# Microcontroller.net
KiCad netlist of a schematic drawn in Altium Designer
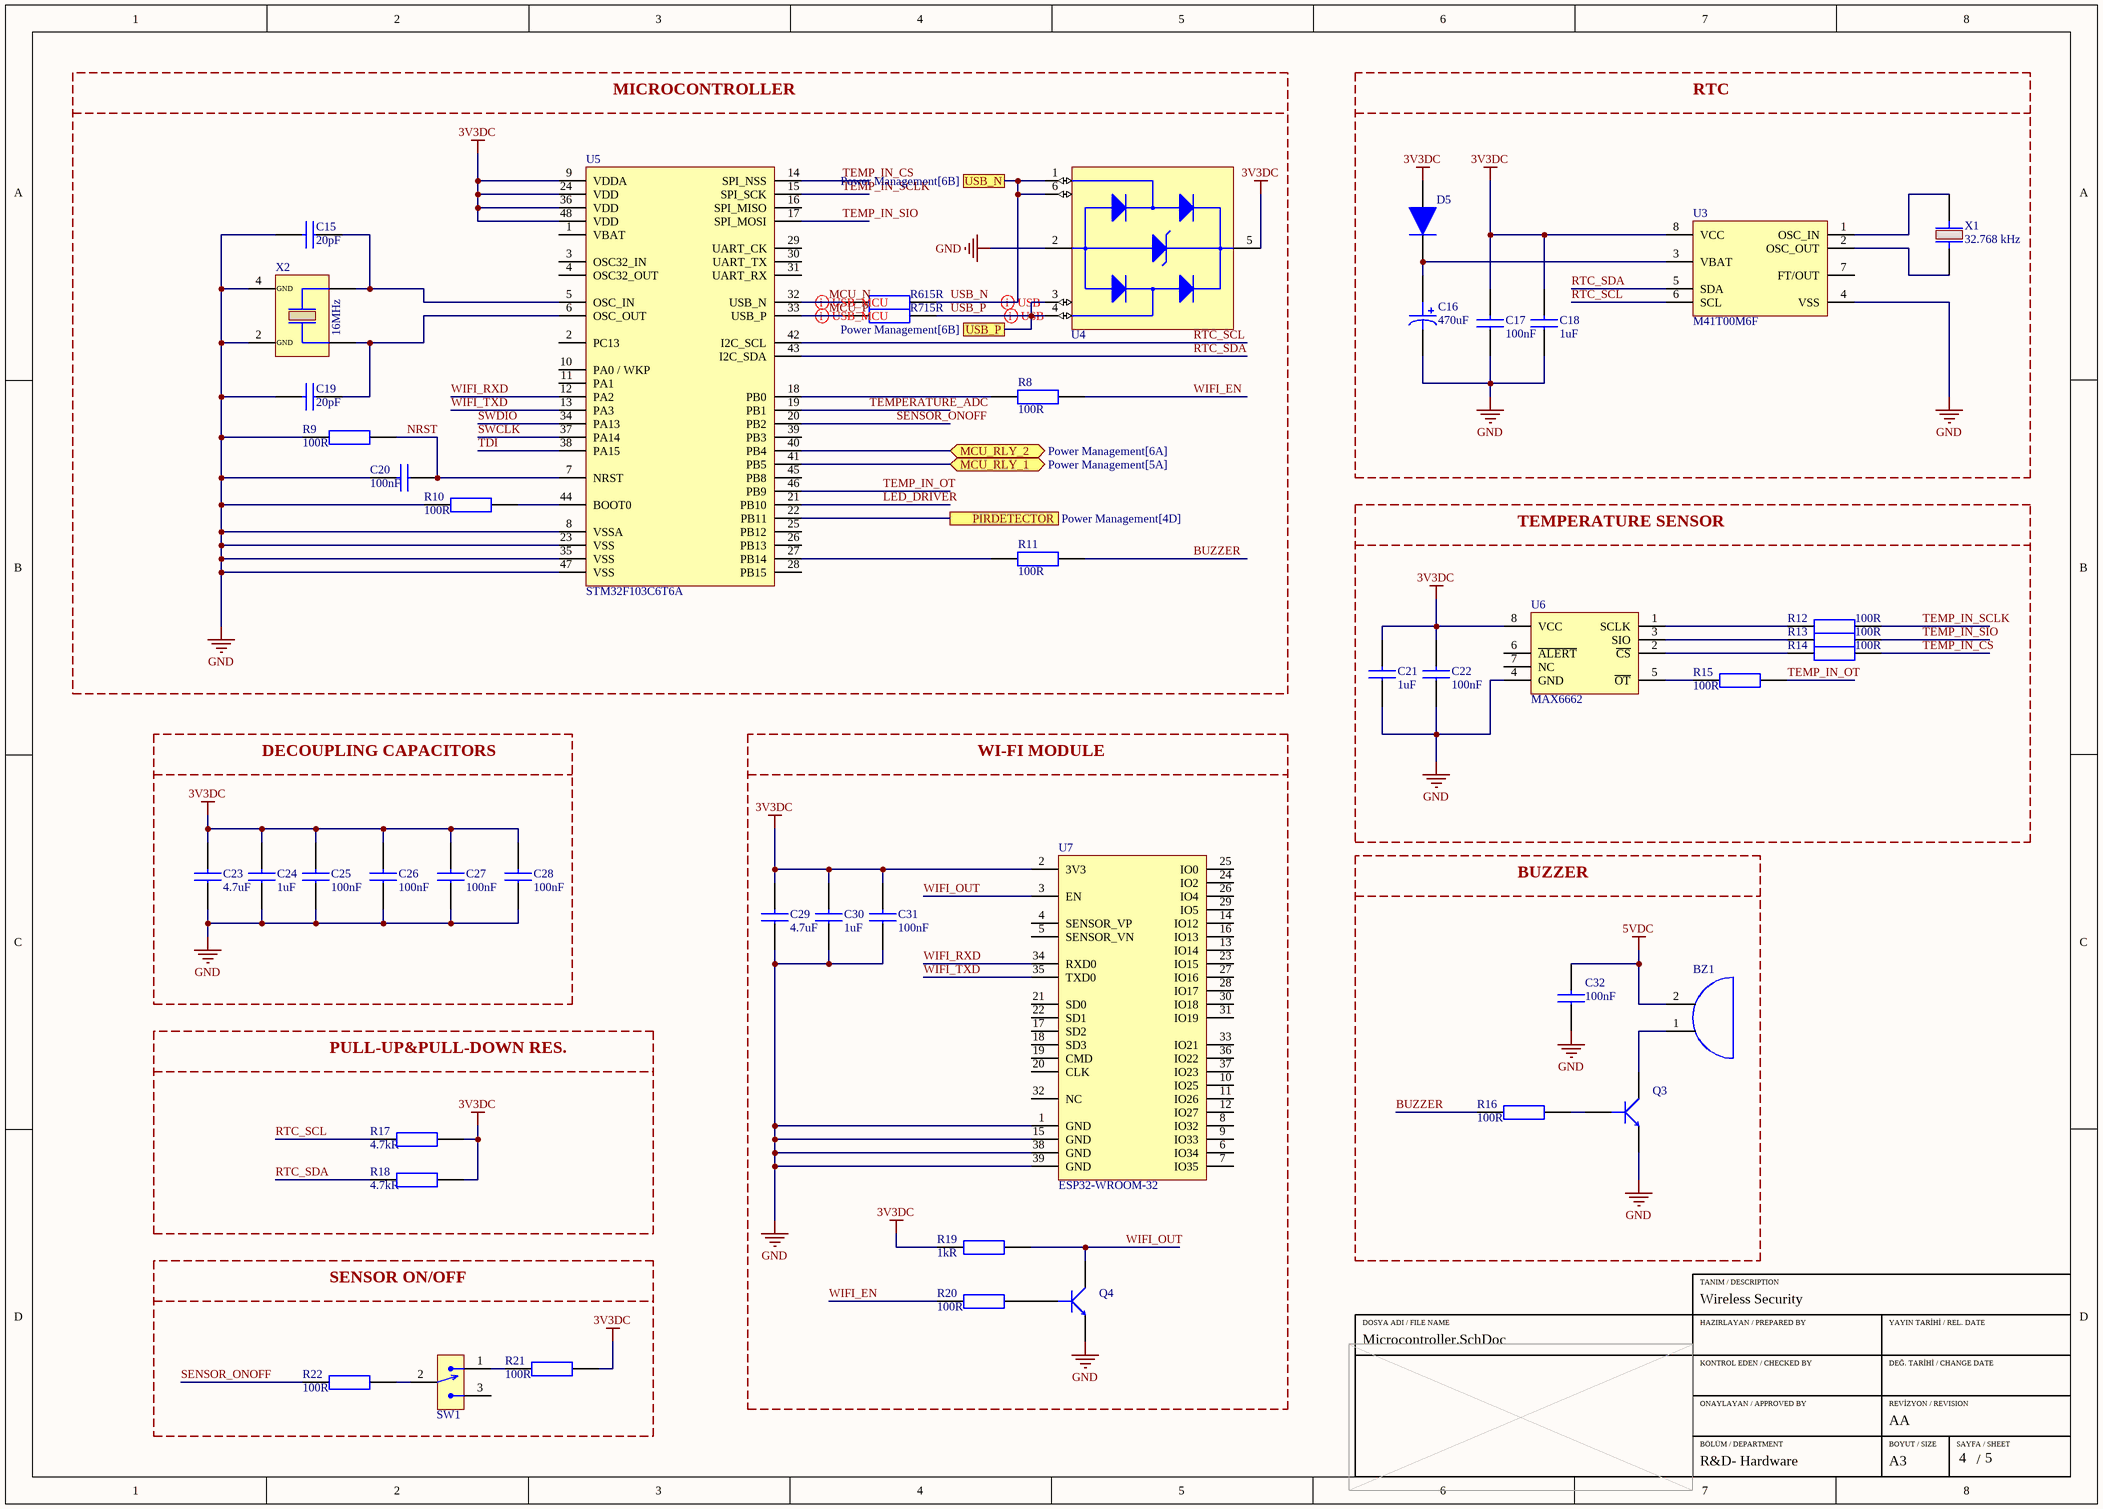
[diagram p0: Microcontroller.SchDoc]

(export (version "E")
  (design (tool "Eeschema 10.0.6"))
  (components
    (comp (ref "BZ1")
      (value "CMI-9605IC-0580T")
      (footprint "CMI-9605IC")
      (description "Buzzers Indicator, Internally Driven Magnetic 5V 30mA 2.7kHz 80dB @ 5V, 10cm Through Hole PC Pins")
      (fields (field (name "MANUFACTURER") "CUI Devices") (field (name "DESIGNED BY") "Cem Uğurcan Özdemir"))
      (libsource (lib "UDEMY_Library") (part "CMI-9605IC-0580T"))
    )
    (comp (ref "C15")
      (value "CL10C200JB8NNNC")
      (footprint "CAP_0603")
      (description "CAP CER 20pF %5 0603 SMD")
      (fields
        (field (name "MANUFACTURER") "Samsung")
        (field (name "TOLERANCE") "5%")
        (field (name "CAPACITANCE") "20pF")
        (field (name "DESIGNED BY") "Cem Uğurcan Özdemir")
      )
      (libsource (lib "UDEMY_Library") (part "CAP CER 20pF 0603"))
    )
    (comp (ref "C16")
      (value "ESH477M050AH4AA")
      (footprint "CAP_RADIAL_D10_P5")
      (description "CAP ALU ELEC 470uF 50V RADIAL")
      (fields
        (field (name "MANUFACTURER") "KEMET")
        (field (name "TOLERANCE") "20%")
        (field (name "CAPACITANCE") "470uF")
        (field (name "DESIGNED BY") "Cem Uğurcan Özdemir")
      )
      (libsource (lib "UDEMY_Library") (part "CAP ALU ELEC 470uF 50V"))
    )
    (comp (ref "C17")
      (value "CL21B104KBCNNNC")
      (footprint "CAP_0805")
      (description "CAP CER 100nF %10 0805")
      (fields
        (field (name "MANUFACTURER") "Samsung")
        (field (name "TOLERANCE") "10%")
        (field (name "CAPACITANCE") "100nF")
        (field (name "DESIGNED BY") "Cem Uğurcan Özdemir")
      )
      (libsource (lib "UDEMY_Library") (part "CAP CER 100nF 0805"))
    )
    (comp (ref "C18")
      (value "CL21B105KBFNNNE")
      (footprint "CAP_0805")
      (description "CAP CER 1uF %10 0805")
      (fields
        (field (name "MANUFACTURER") "Samsung")
        (field (name "TOLERANCE") "10%")
        (field (name "CAPACITANCE") "1uF")
        (field (name "DESIGNED BY") "Cem Uğurcan Özdemir")
      )
      (libsource (lib "UDEMY_Library") (part "CAP CER 1uF 0805"))
    )
    (comp (ref "C19")
      (value "CL10C200JB8NNNC")
      (footprint "CAP_0603")
      (description "CAP CER 20pF %5 0603 SMD")
      (fields
        (field (name "MANUFACTURER") "Samsung")
        (field (name "TOLERANCE") "5%")
        (field (name "CAPACITANCE") "20pF")
        (field (name "DESIGNED BY") "Cem Uğurcan Özdemir")
      )
      (libsource (lib "UDEMY_Library") (part "CAP CER 20pF 0603"))
    )
    (comp (ref "C20")
      (value "C0603C104K5RACTU")
      (footprint "CAP_0603")
      (description "CAP CER 100nF %10 0603 SMD")
      (fields
        (field (name "MANUFACTURER") "KEMET")
        (field (name "TOLERANCE") "10%")
        (field (name "CAPACITANCE") "100nF")
        (field (name "DESIGNED BY") "Cem Uğurcan Özdemir")
      )
      (libsource (lib "UDEMY_Library") (part "CAP CER 100nF 0603"))
    )
    (comp (ref "C21")
      (value "CL21B105KBFNNNE")
      (footprint "CAP_0805")
      (description "CAP CER 1uF %10 0805")
      (fields
        (field (name "MANUFACTURER") "Samsung")
        (field (name "TOLERANCE") "10%")
        (field (name "CAPACITANCE") "1uF")
        (field (name "DESIGNED BY") "Cem Uğurcan Özdemir")
      )
      (libsource (lib "UDEMY_Library") (part "CAP CER 1uF 0805"))
    )
    (comp (ref "C22")
      (value "CL21B104KBCNNNC")
      (footprint "CAP_0805")
      (description "CAP CER 100nF %10 0805")
      (fields
        (field (name "MANUFACTURER") "Samsung")
        (field (name "TOLERANCE") "10%")
        (field (name "CAPACITANCE") "100nF")
        (field (name "DESIGNED BY") "Cem Uğurcan Özdemir")
      )
      (libsource (lib "UDEMY_Library") (part "CAP CER 100nF 0805"))
    )
    (comp (ref "C23")
      (value "CL21A475KAQNNNE")
      (footprint "CAP_0805")
      (description "CAP CER 4.7uF %10 0805")
      (fields
        (field (name "MANUFACTURER") "Samsung")
        (field (name "TOLERANCE") "10%")
        (field (name "CAPACITANCE") "4.7uF")
        (field (name "DESIGNED BY") "Cem Uğurcan Özdemir")
      )
      (libsource (lib "UDEMY_Library") (part "CAP CER 4.7uF 0805"))
    )
    (comp (ref "C24")
      (value "CL21B105KBFNNNE")
      (footprint "CAP_0805")
      (description "CAP CER 1uF %10 0805")
      (fields
        (field (name "MANUFACTURER") "Samsung")
        (field (name "TOLERANCE") "10%")
        (field (name "CAPACITANCE") "1uF")
        (field (name "DESIGNED BY") "Cem Uğurcan Özdemir")
      )
      (libsource (lib "UDEMY_Library") (part "CAP CER 1uF 0805"))
    )
    (comp (ref "C25")
      (value "C0603C104K5RACTU")
      (footprint "CAP_0603")
      (description "CAP CER 100nF %10 0603 SMD")
      (fields
        (field (name "MANUFACTURER") "KEMET")
        (field (name "TOLERANCE") "10%")
        (field (name "CAPACITANCE") "100nF")
        (field (name "DESIGNED BY") "Cem Uğurcan Özdemir")
      )
      (libsource (lib "UDEMY_Library") (part "CAP CER 100nF 0603"))
    )
    (comp (ref "C26")
      (value "C0603C104K5RACTU")
      (footprint "CAP_0603")
      (description "CAP CER 100nF %10 0603 SMD")
      (fields
        (field (name "MANUFACTURER") "KEMET")
        (field (name "TOLERANCE") "10%")
        (field (name "CAPACITANCE") "100nF")
        (field (name "DESIGNED BY") "Cem Uğurcan Özdemir")
      )
      (libsource (lib "UDEMY_Library") (part "CAP CER 100nF 0603"))
    )
    (comp (ref "C27")
      (value "C0603C104K5RACTU")
      (footprint "CAP_0603")
      (description "CAP CER 100nF %10 0603 SMD")
      (fields
        (field (name "MANUFACTURER") "KEMET")
        (field (name "TOLERANCE") "10%")
        (field (name "CAPACITANCE") "100nF")
        (field (name "DESIGNED BY") "Cem Uğurcan Özdemir")
      )
      (libsource (lib "UDEMY_Library") (part "CAP CER 100nF 0603"))
    )
    (comp (ref "C28")
      (value "C0603C104K5RACTU")
      (footprint "CAP_0603")
      (description "CAP CER 100nF %10 0603 SMD")
      (fields
        (field (name "MANUFACTURER") "KEMET")
        (field (name "TOLERANCE") "10%")
        (field (name "CAPACITANCE") "100nF")
        (field (name "DESIGNED BY") "Cem Uğurcan Özdemir")
      )
      (libsource (lib "UDEMY_Library") (part "CAP CER 100nF 0603"))
    )
    (comp (ref "C29")
      (value "CL21A475KAQNNNE")
      (footprint "CAP_0805")
      (description "CAP CER 4.7uF %10 0805")
      (fields
        (field (name "MANUFACTURER") "Samsung")
        (field (name "TOLERANCE") "10%")
        (field (name "CAPACITANCE") "4.7uF")
        (field (name "DESIGNED BY") "Cem Uğurcan Özdemir")
      )
      (libsource (lib "UDEMY_Library") (part "CAP CER 4.7uF 0805"))
    )
    (comp (ref "C30")
      (value "CL21B105KBFNNNE")
      (footprint "CAP_0805")
      (description "CAP CER 1uF %10 0805")
      (fields
        (field (name "MANUFACTURER") "Samsung")
        (field (name "TOLERANCE") "10%")
        (field (name "CAPACITANCE") "1uF")
        (field (name "DESIGNED BY") "Cem Uğurcan Özdemir")
      )
      (libsource (lib "UDEMY_Library") (part "CAP CER 1uF 0805"))
    )
    (comp (ref "C31")
      (value "CL21B104KBCNNNC")
      (footprint "CAP_0805")
      (description "CAP CER 100nF %10 0805")
      (fields
        (field (name "MANUFACTURER") "Samsung")
        (field (name "TOLERANCE") "10%")
        (field (name "CAPACITANCE") "100nF")
        (field (name "DESIGNED BY") "Cem Uğurcan Özdemir")
      )
      (libsource (lib "UDEMY_Library") (part "CAP CER 100nF 0805"))
    )
    (comp (ref "C32")
      (value "CL21B104KBCNNNC")
      (footprint "CAP_0805")
      (description "CAP CER 100nF %10 0805")
      (fields
        (field (name "MANUFACTURER") "Samsung")
        (field (name "TOLERANCE") "10%")
        (field (name "CAPACITANCE") "100nF")
        (field (name "DESIGNED BY") "Cem Uğurcan Özdemir")
      )
      (libsource (lib "UDEMY_Library") (part "CAP CER 100nF 0805"))
    )
    (comp (ref "D5")
      (value "1N4148WS")
      (footprint "SOD323F")
      (description "Diode, Single, 75 V, 150 mA, 1 V, 4 ns")
      (fields
        (field (name "MANUFACTURER") "ON Semiconductor / Fairchild")
        (field (name "DESIGNED BY") "Cem Uğurcan Özdemir")
      )
      (libsource (lib "UDEMY_Library") (part "1N4148WS"))
    )
    (comp (ref "Q3")
      (value "MMBT3904-7-F")
      (footprint "SOT-23F")
      (description "Transistor General Purpose BJT NPN 40 Volt 0.2A Automotive 3-Pin SOT-23")
      (fields (field (name "MANUFACTURER") "Diodes Zetex") (field (name "DESIGNED BY") "Cem Uğurcan Özdemir"))
      (libsource (lib "UDEMY_Library") (part "MMBT3904-7-F"))
    )
    (comp (ref "Q4")
      (value "MMBT3904-7-F")
      (footprint "SOT-23F")
      (description "Transistor General Purpose BJT NPN 40 Volt 0.2A Automotive 3-Pin SOT-23")
      (fields (field (name "MANUFACTURER") "Diodes Zetex") (field (name "DESIGNED BY") "Cem Uğurcan Özdemir"))
      (libsource (lib "UDEMY_Library") (part "MMBT3904-7-F"))
    )
    (comp (ref "R6")
      (value "RC0603JR-0715RL")
      (footprint "RES_0603")
      (description "RES 15 %5 OHM 0603 SMD")
      (fields
        (field (name "MANUFACTURER") "Yageo")
        (field (name "TOLERANCE") "5%")
        (field (name "RESISTANCE") "15R")
        (field (name "DESIGNED BY") "Cem Uğurcan Özdemir")
      )
      (libsource (lib "UDEMY_Library") (part "RES 15 OHM 0603"))
    )
    (comp (ref "R7")
      (value "RC0603JR-0715RL")
      (footprint "RES_0603")
      (description "RES 15 %5 OHM 0603 SMD")
      (fields
        (field (name "MANUFACTURER") "Yageo")
        (field (name "TOLERANCE") "5%")
        (field (name "RESISTANCE") "15R")
        (field (name "DESIGNED BY") "Cem Uğurcan Özdemir")
      )
      (libsource (lib "UDEMY_Library") (part "RES 15 OHM 0603"))
    )
    (comp (ref "R8")
      (value "RC0603JR-07100RL")
      (footprint "RES_0603")
      (description "RES 100 %5 OHM 0603 SMD")
      (fields
        (field (name "MANUFACTURER") "Yageo")
        (field (name "TOLERANCE") "5%")
        (field (name "RESISTANCE") "100R")
        (field (name "DESIGNED BY") "Cem Uğurcan Özdemir")
      )
      (libsource (lib "UDEMY_Library") (part "RES 100 OHM 0603"))
    )
    (comp (ref "R9")
      (value "RC0603JR-07100RL")
      (footprint "RES_0603")
      (description "RES 100 %5 OHM 0603 SMD")
      (fields
        (field (name "MANUFACTURER") "Yageo")
        (field (name "TOLERANCE") "5%")
        (field (name "RESISTANCE") "100R")
        (field (name "DESIGNED BY") "Cem Uğurcan Özdemir")
      )
      (libsource (lib "UDEMY_Library") (part "RES 100 OHM 0603"))
    )
    (comp (ref "R10")
      (value "RC0603JR-07100RL")
      (footprint "RES_0603")
      (description "RES 100 %5 OHM 0603 SMD")
      (fields
        (field (name "MANUFACTURER") "Yageo")
        (field (name "TOLERANCE") "5%")
        (field (name "RESISTANCE") "100R")
        (field (name "DESIGNED BY") "Cem Uğurcan Özdemir")
      )
      (libsource (lib "UDEMY_Library") (part "RES 100 OHM 0603"))
    )
    (comp (ref "R11")
      (value "RC0603JR-07100RL")
      (footprint "RES_0603")
      (description "RES 100 %5 OHM 0603 SMD")
      (fields
        (field (name "MANUFACTURER") "Yageo")
        (field (name "TOLERANCE") "5%")
        (field (name "RESISTANCE") "100R")
        (field (name "DESIGNED BY") "Cem Uğurcan Özdemir")
      )
      (libsource (lib "UDEMY_Library") (part "RES 100 OHM 0603"))
    )
    (comp (ref "R12")
      (value "RC0603JR-07100RL")
      (footprint "RES_0603")
      (description "RES 100 %5 OHM 0603 SMD")
      (fields
        (field (name "MANUFACTURER") "Yageo")
        (field (name "TOLERANCE") "5%")
        (field (name "RESISTANCE") "100R")
        (field (name "DESIGNED BY") "Cem Uğurcan Özdemir")
      )
      (libsource (lib "UDEMY_Library") (part "RES 100 OHM 0603"))
    )
    (comp (ref "R13")
      (value "RC0603JR-07100RL")
      (footprint "RES_0603")
      (description "RES 100 %5 OHM 0603 SMD")
      (fields
        (field (name "MANUFACTURER") "Yageo")
        (field (name "TOLERANCE") "5%")
        (field (name "RESISTANCE") "100R")
        (field (name "DESIGNED BY") "Cem Uğurcan Özdemir")
      )
      (libsource (lib "UDEMY_Library") (part "RES 100 OHM 0603"))
    )
    (comp (ref "R14")
      (value "RC0603JR-07100RL")
      (footprint "RES_0603")
      (description "RES 100 %5 OHM 0603 SMD")
      (fields
        (field (name "MANUFACTURER") "Yageo")
        (field (name "TOLERANCE") "5%")
        (field (name "RESISTANCE") "100R")
        (field (name "DESIGNED BY") "Cem Uğurcan Özdemir")
      )
      (libsource (lib "UDEMY_Library") (part "RES 100 OHM 0603"))
    )
    (comp (ref "R15")
      (value "RC0603JR-07100RL")
      (footprint "RES_0603")
      (description "RES 100 %5 OHM 0603 SMD")
      (fields
        (field (name "MANUFACTURER") "Yageo")
        (field (name "TOLERANCE") "5%")
        (field (name "RESISTANCE") "100R")
        (field (name "DESIGNED BY") "Cem Uğurcan Özdemir")
      )
      (libsource (lib "UDEMY_Library") (part "RES 100 OHM 0603"))
    )
    (comp (ref "R16")
      (value "RC0603JR-07100RL")
      (footprint "RES_0603")
      (description "RES 100 %5 OHM 0603 SMD")
      (fields
        (field (name "MANUFACTURER") "Yageo")
        (field (name "TOLERANCE") "5%")
        (field (name "RESISTANCE") "100R")
        (field (name "DESIGNED BY") "Cem Uğurcan Özdemir")
      )
      (libsource (lib "UDEMY_Library") (part "RES 100 OHM 0603"))
    )
    (comp (ref "R17")
      (value "RC0603JR-074K7L")
      (footprint "RES_0603")
      (description "RES 4K7 %5 OHM 0603 SMD")
      (fields
        (field (name "MANUFACTURER") "Yageo")
        (field (name "TOLERANCE") "5%")
        (field (name "RESISTANCE") "4.7kR")
        (field (name "DESIGNED BY") "Cem Uğurcan Özdemir")
      )
      (libsource (lib "UDEMY_Library") (part "RES 4K7 OHM 0603"))
    )
    (comp (ref "R18")
      (value "RC0603JR-074K7L")
      (footprint "RES_0603")
      (description "RES 4K7 %5 OHM 0603 SMD")
      (fields
        (field (name "MANUFACTURER") "Yageo")
        (field (name "TOLERANCE") "5%")
        (field (name "RESISTANCE") "4.7kR")
        (field (name "DESIGNED BY") "Cem Uğurcan Özdemir")
      )
      (libsource (lib "UDEMY_Library") (part "RES 4K7 OHM 0603"))
    )
    (comp (ref "R19")
      (value "RC0603FR-0710KL")
      (footprint "RES_0603")
      (description "RES 1K %1 OHM 0603 SMD")
      (fields
        (field (name "MANUFACTURER") "Yageo")
        (field (name "MANUFACTURER PART NUMBER") "RC0603JR-071KL")
        (field (name "RESISTANCE") "1kR")
        (field (name "DESIGNED BY") "Cem Uğurcan Özdemir")
      )
      (libsource (lib "UDEMY_Library") (part "RES 1K OHM 0603"))
    )
    (comp (ref "R20")
      (value "RC0603JR-07100RL")
      (footprint "RES_0603")
      (description "RES 100 %5 OHM 0603 SMD")
      (fields
        (field (name "MANUFACTURER") "Yageo")
        (field (name "TOLERANCE") "5%")
        (field (name "RESISTANCE") "100R")
        (field (name "DESIGNED BY") "Cem Uğurcan Özdemir")
      )
      (libsource (lib "UDEMY_Library") (part "RES 100 OHM 0603"))
    )
    (comp (ref "R21")
      (value "RC0603JR-07100RL")
      (footprint "RES_0603")
      (description "RES 100 %5 OHM 0603 SMD")
      (fields
        (field (name "MANUFACTURER") "Yageo")
        (field (name "TOLERANCE") "5%")
        (field (name "RESISTANCE") "100R")
        (field (name "DESIGNED BY") "Cem Uğurcan Özdemir")
      )
      (libsource (lib "UDEMY_Library") (part "RES 100 OHM 0603"))
    )
    (comp (ref "R22")
      (value "RC0603JR-07100RL")
      (footprint "RES_0603")
      (description "RES 100 %5 OHM 0603 SMD")
      (fields
        (field (name "MANUFACTURER") "Yageo")
        (field (name "TOLERANCE") "5%")
        (field (name "RESISTANCE") "100R")
        (field (name "DESIGNED BY") "Cem Uğurcan Özdemir")
      )
      (libsource (lib "") (part "RES 100 OHM 0603_1"))
    )
    (comp (ref "SW1")
      (value "EG1215AA")
      (footprint "EG1215AA")
      (description "Slide Switch, SPDT, 0.025A, 24V, SMD")
      (fields
        (field (name "MANUFACTURER") "E-Switch")
        (field (name "TOLERANCE") "4.95%")
        (field (name "DESIGNED BY") "Cem Uğurcan Özdemir")
      )
      (libsource (lib "UDEMY_Library") (part "EG1215AA"))
    )
    (comp (ref "U3")
      (value "M41T00M6F")
      (footprint "SOIC8")
      (description "IC RTC CLK/CALENDAR I2C 8-SOIC")
      (fields
        (field (name "MANUFACTURER") "STMicroelectronics")
        (field (name "DESIGNED BY") "Cem Uğurcan Özdemir")
      )
      (libsource (lib "UDEMY_Library") (part "M41T00M6F"))
    )
    (comp (ref "U4")
      (value "USBLC6-2SC6")
      (footprint "SOT23-6L")
      (description "TVS DIODE 5.25V 17V SOT23-6")
      (fields
        (field (name "MANUFACTURER") "STMicroelectronics")
        (field (name "DESIGNED BY") "Cem Uğurcan Özdemir")
      )
      (libsource (lib "UDEMY_Library") (part "USB PROTECTION"))
    )
    (comp (ref "U5")
      (value "STM32F103C6T6A")
      (footprint "LQFP-48")
      (description "MCU 32-bit STM32F ARM Cortex M3 RISC 32KB Flash 2.5V/3.3V 48-Pin LQFP Tray")
      (fields
        (field (name "MANUFACTURER") "STMicroelectronics")
        (field (name "DESIGNED BY") "Cem Uğurcan Özdemir")
      )
      (libsource (lib "UDEMY_Library") (part "STM32F103C6T6A"))
    )
    (comp (ref "U6")
      (value "MAX6662")
      (footprint "SOIC8")
      (description "SENSOR TEMPERATURE SPI 8SOIC")
      (fields
        (field (name "MANUFACTURER") "Maxim")
        (field (name "MANUFACTURER PART NUMBER") "MAX6662MSA+")
        (field (name "DESIGNED BY") "Cem Uğurcan Özdemir")
      )
      (libsource (lib "UDEMY_Library") (part "MAX6662"))
    )
    (comp (ref "U7")
      (value "ESP32-WROOM-32")
      (footprint "ESP32-32")
      (description "SMD MODULE, ESP32-D0WDQ6, 32MBIT")
      (fields
        (field (name "MANUFACTURER") "Espressif Systems")
        (field (name "DESIGNED BY") "Cem Uğurcan Özdemir")
      )
      (libsource (lib "UDEMY_Library") (part "ESP32-WROOM-32"))
    )
    (comp (ref "X1")
      (value "ABS05-32.768KHZ-T")
      (footprint "ABS05")
      (description "Crystal, 32.768 kHz, SMD, 1.6mm x 1mm, 12.5 pF, 20 ppm, ABS05 Series")
      (fields
        (field (name "MANUFACTURER") "Abracon")
        (field (name "TOLERANCE") "20ppm")
        (field (name "OPERATING FREQUENCY") "32.768 kHz")
        (field (name "DESIGNED BY") "Cem Uğurcan Özdemir")
      )
      (libsource (lib "UDEMY_Library") (part "CRYSTAL 32768kHZ"))
    )
    (comp (ref "X2")
      (value "ECS-160-20-30B-TR")
      (footprint "ECS")
      (description "CRYSTAL 16.0000MHZ 20PF SMD")
      (fields
        (field (name "MANUFACTURER") "ECS International")
        (field (name "TOLERANCE") "50ppm")
        (field (name "FREQUENCY") "16MHz")
        (field (name "DESIGNED BY") "Cem Uğurcan Özdemir")
      )
      (libsource (lib "UDEMY_Library") (part "CRYSTAL 16MHz"))
    )
  )
  (nets
    (net (code "1") (name "/BUZZER") (class "Default")
      (node (ref "R11") (pin "2") (pinfunction "2_2") (pintype "passive"))
      (node (ref "R16") (pin "1") (pinfunction "1_1") (pintype "passive"))
    )
    (net (code "2") (name "/LED_DRIVER") (class "Default")
      (node (ref "U5") (pin "21") (pinfunction "PB10_21") (pintype "passive"))
    )
    (net (code "3") (name "/MCU_N") (class "Default")
      (node (ref "R6") (pin "1") (pinfunction "1_1") (pintype "passive"))
      (node (ref "U5") (pin "32") (pinfunction "USB_N_32") (pintype "passive"))
    )
    (net (code "4") (name "/MCU_P") (class "Default")
      (node (ref "R7") (pin "1") (pinfunction "1_1") (pintype "passive"))
      (node (ref "U5") (pin "33") (pinfunction "USB_P_33") (pintype "passive"))
    )
    (net (code "5") (name "/MCU_RLY_1") (class "Default")
      (node (ref "U5") (pin "41") (pinfunction "PB5_41") (pintype "passive"))
    )
    (net (code "6") (name "/MCU_RLY_2") (class "Default")
      (node (ref "U5") (pin "40") (pinfunction "PB4_40") (pintype "passive"))
    )
    (net (code "7") (name "/NRST") (class "Default")
      (node (ref "C20") (pin "1") (pinfunction "1_1") (pintype "passive"))
      (node (ref "R9") (pin "2") (pinfunction "2_2") (pintype "passive"))
      (node (ref "U5") (pin "7") (pinfunction "NRST_7") (pintype "passive"))
    )
    (net (code "8") (name "/PIRDETECTOR") (class "Default")
      (node (ref "U5") (pin "22") (pinfunction "PB11_22") (pintype "passive"))
    )
    (net (code "9") (name "/RTC_SCL") (class "Default")
      (node (ref "R17") (pin "1") (pinfunction "1_1") (pintype "passive"))
      (node (ref "U3") (pin "6") (pinfunction "SCL_6") (pintype "passive"))
      (node (ref "U5") (pin "42") (pinfunction "I2C_SCL_42") (pintype "passive"))
    )
    (net (code "10") (name "/RTC_SDA") (class "Default")
      (node (ref "R18") (pin "1") (pinfunction "1_1") (pintype "passive"))
      (node (ref "U3") (pin "5") (pinfunction "SDA_5") (pintype "passive"))
      (node (ref "U5") (pin "43") (pinfunction "I2C_SDA_43") (pintype "passive"))
    )
    (net (code "11") (name "/SENSOR_ONOFF") (class "Default")
      (node (ref "R22") (pin "2") (pinfunction "2_2") (pintype "passive"))
      (node (ref "U5") (pin "20") (pinfunction "PB2_20") (pintype "passive"))
    )
    (net (code "12") (name "/SWCLK") (class "Default")
      (node (ref "U5") (pin "37") (pinfunction "PA14_37") (pintype "passive"))
    )
    (net (code "13") (name "/SWDIO") (class "Default")
      (node (ref "U5") (pin "34") (pinfunction "PA13_34") (pintype "passive"))
    )
    (net (code "14") (name "/TDI") (class "Default")
      (node (ref "U5") (pin "38") (pinfunction "PA15_38") (pintype "passive"))
    )
    (net (code "15") (name "/TEMPERATURE_ADC") (class "Default")
      (node (ref "U5") (pin "19") (pinfunction "PB1_19") (pintype "passive"))
    )
    (net (code "16") (name "/TEMP_IN_CS") (class "Default")
      (node (ref "R14") (pin "2") (pinfunction "2_2") (pintype "passive"))
      (node (ref "U5") (pin "14") (pinfunction "SPI_NSS_14") (pintype "passive"))
    )
    (net (code "17") (name "/TEMP_IN_OT") (class "Default")
      (node (ref "R15") (pin "2") (pinfunction "2_2") (pintype "passive"))
      (node (ref "U5") (pin "46") (pinfunction "PB9_46") (pintype "passive"))
    )
    (net (code "18") (name "/TEMP_IN_SCLK") (class "Default")
      (node (ref "R12") (pin "2") (pinfunction "2_2") (pintype "passive"))
      (node (ref "U5") (pin "15") (pinfunction "SPI_SCK_15") (pintype "passive"))
    )
    (net (code "19") (name "/TEMP_IN_SIO") (class "Default")
      (node (ref "R13") (pin "2") (pinfunction "2_2") (pintype "passive"))
      (node (ref "U5") (pin "17") (pinfunction "SPI_MOSI_17") (pintype "passive"))
    )
    (net (code "20") (name "/USB_N") (class "Default")
      (node (ref "R6") (pin "2") (pinfunction "2_2") (pintype "passive"))
      (node (ref "U4") (pin "1") (pinfunction "I/O1_1") (pintype "bidirectional"))
      (node (ref "U4") (pin "6") (pinfunction "I/O1_6") (pintype "bidirectional"))
    )
    (net (code "21") (name "/USB_P") (class "Default")
      (node (ref "R7") (pin "2") (pinfunction "2_2") (pintype "passive"))
      (node (ref "U4") (pin "3") (pinfunction "I/O2_3") (pintype "bidirectional"))
      (node (ref "U4") (pin "4") (pinfunction "I/O2_4") (pintype "bidirectional"))
    )
    (net (code "22") (name "/WIFI_EN") (class "Default")
      (node (ref "R20") (pin "1") (pinfunction "1_1") (pintype "passive"))
      (node (ref "R8") (pin "2") (pinfunction "2_2") (pintype "passive"))
    )
    (net (code "23") (name "/WIFI_OUT") (class "Default")
      (node (ref "Q4") (pin "3") (pinfunction "C_3") (pintype "power_in"))
      (node (ref "R19") (pin "1") (pinfunction "1_1") (pintype "passive"))
      (node (ref "U7") (pin "3") (pinfunction "EN_3") (pintype "passive"))
    )
    (net (code "24") (name "/WIFI_RXD") (class "Default")
      (node (ref "U5") (pin "12") (pinfunction "PA2_12") (pintype "passive"))
      (node (ref "U7") (pin "34") (pinfunction "RXD0_34") (pintype "passive"))
    )
    (net (code "25") (name "/WIFI_TXD") (class "Default")
      (node (ref "U5") (pin "13") (pinfunction "PA3_13") (pintype "passive"))
      (node (ref "U7") (pin "35") (pinfunction "TXD0_35") (pintype "passive"))
    )
    (net (code "26") (name "3V3DC") (class "Default")
      (node (ref "C17") (pin "2") (pinfunction "2_2") (pintype "passive"))
      (node (ref "C18") (pin "2") (pinfunction "2_2") (pintype "passive"))
      (node (ref "C21") (pin "2") (pinfunction "2_2") (pintype "passive"))
      (node (ref "C22") (pin "2") (pinfunction "2_2") (pintype "passive"))
      (node (ref "C23") (pin "2") (pinfunction "2_2") (pintype "passive"))
      (node (ref "C24") (pin "2") (pinfunction "2_2") (pintype "passive"))
      (node (ref "C25") (pin "2") (pinfunction "2_2") (pintype "passive"))
      (node (ref "C26") (pin "2") (pinfunction "2_2") (pintype "passive"))
      (node (ref "C27") (pin "2") (pinfunction "2_2") (pintype "passive"))
      (node (ref "C28") (pin "2") (pinfunction "2_2") (pintype "passive"))
      (node (ref "C29") (pin "2") (pinfunction "2_2") (pintype "passive"))
      (node (ref "C30") (pin "2") (pinfunction "2_2") (pintype "passive"))
      (node (ref "C31") (pin "2") (pinfunction "2_2") (pintype "passive"))
      (node (ref "D5") (pin "2") (pinfunction "2_2") (pintype "power_in"))
      (node (ref "R17") (pin "2") (pinfunction "2_2") (pintype "passive"))
      (node (ref "R18") (pin "2") (pinfunction "2_2") (pintype "passive"))
      (node (ref "R19") (pin "2") (pinfunction "2_2") (pintype "passive"))
      (node (ref "R21") (pin "2") (pinfunction "2_2") (pintype "passive"))
      (node (ref "U3") (pin "8") (pinfunction "VCC_8") (pintype "passive"))
      (node (ref "U4") (pin "5") (pinfunction "VBUS_5") (pintype "power_in"))
      (node (ref "U5") (pin "24") (pinfunction "VDD_24") (pintype "passive"))
      (node (ref "U5") (pin "36") (pinfunction "VDD_36") (pintype "passive"))
      (node (ref "U5") (pin "48") (pinfunction "VDD_48") (pintype "passive"))
      (node (ref "U5") (pin "9") (pinfunction "VDDA_9") (pintype "passive"))
      (node (ref "U6") (pin "8") (pinfunction "VCC_8") (pintype "passive"))
      (node (ref "U7") (pin "2") (pinfunction "3V3_2") (pintype "passive"))
    )
    (net (code "27") (name "5VDC") (class "Default")
      (node (ref "BZ1") (pin "2") (pinfunction "2_2") (pintype "passive"))
      (node (ref "C32") (pin "2") (pinfunction "2_2") (pintype "passive"))
    )
    (net (code "28") (name "GND") (class "Default")
      (node (ref "C15") (pin "2") (pinfunction "2_2") (pintype "passive"))
      (node (ref "C16") (pin "2") (pinfunction "2_2") (pintype "passive"))
      (node (ref "C17") (pin "1") (pinfunction "1_1") (pintype "passive"))
      (node (ref "C18") (pin "1") (pinfunction "1_1") (pintype "passive"))
      (node (ref "C19") (pin "2") (pinfunction "2_2") (pintype "passive"))
      (node (ref "C20") (pin "2") (pinfunction "2_2") (pintype "passive"))
      (node (ref "C21") (pin "1") (pinfunction "1_1") (pintype "passive"))
      (node (ref "C22") (pin "1") (pinfunction "1_1") (pintype "passive"))
      (node (ref "C23") (pin "1") (pinfunction "1_1") (pintype "passive"))
      (node (ref "C24") (pin "1") (pinfunction "1_1") (pintype "passive"))
      (node (ref "C25") (pin "1") (pinfunction "1_1") (pintype "passive"))
      (node (ref "C26") (pin "1") (pinfunction "1_1") (pintype "passive"))
      (node (ref "C27") (pin "1") (pinfunction "1_1") (pintype "passive"))
      (node (ref "C28") (pin "1") (pinfunction "1_1") (pintype "passive"))
      (node (ref "C29") (pin "1") (pinfunction "1_1") (pintype "passive"))
      (node (ref "C30") (pin "1") (pinfunction "1_1") (pintype "passive"))
      (node (ref "C31") (pin "1") (pinfunction "1_1") (pintype "passive"))
      (node (ref "C32") (pin "1") (pinfunction "1_1") (pintype "passive"))
      (node (ref "Q3") (pin "2") (pinfunction "E_2") (pintype "power_in"))
      (node (ref "Q4") (pin "2") (pinfunction "E_2") (pintype "power_in"))
      (node (ref "R10") (pin "1") (pinfunction "1_1") (pintype "passive"))
      (node (ref "R9") (pin "1") (pinfunction "1_1") (pintype "passive"))
      (node (ref "U3") (pin "4") (pinfunction "VSS_4") (pintype "passive"))
      (node (ref "U4") (pin "2") (pinfunction "GND_2") (pintype "power_in"))
      (node (ref "U5") (pin "23") (pinfunction "VSS_23") (pintype "passive"))
      (node (ref "U5") (pin "35") (pinfunction "VSS_35") (pintype "passive"))
      (node (ref "U5") (pin "47") (pinfunction "VSS_47") (pintype "passive"))
      (node (ref "U5") (pin "8") (pinfunction "VSSA_8") (pintype "passive"))
      (node (ref "U6") (pin "4") (pinfunction "GND_4") (pintype "passive"))
      (node (ref "U7") (pin "1") (pinfunction "GND_1") (pintype "passive"))
      (node (ref "U7") (pin "15") (pinfunction "GND_15") (pintype "passive"))
      (node (ref "U7") (pin "38") (pinfunction "GND_38") (pintype "passive"))
      (node (ref "U7") (pin "39") (pinfunction "GND_39") (pintype "passive"))
      (node (ref "X2") (pin "2") (pinfunction "GND_2") (pintype "passive"))
      (node (ref "X2") (pin "4") (pinfunction "GND_4") (pintype "passive"))
    )
    (net (code "29") (name "Net-(Q3-B)") (class "Default")
      (node (ref "Q3") (pin "1") (pinfunction "B_1") (pintype "power_in"))
      (node (ref "R16") (pin "2") (pinfunction "2_2") (pintype "passive"))
    )
    (net (code "30") (name "Net-(Q3-C)") (class "Default")
      (node (ref "BZ1") (pin "1") (pinfunction "1_1") (pintype "passive"))
      (node (ref "Q3") (pin "3") (pinfunction "C_3") (pintype "power_in"))
    )
    (net (code "31") (name "Net-(Q4-B)") (class "Default")
      (node (ref "Q4") (pin "1") (pinfunction "B_1") (pintype "power_in"))
      (node (ref "R20") (pin "2") (pinfunction "2_2") (pintype "passive"))
    )
    (net (code "32") (name "Net-(R21-Pad1)") (class "Default")
      (node (ref "R21") (pin "1") (pinfunction "1_1") (pintype "passive"))
      (node (ref "SW1") (pin "1") (pinfunction "1_1") (pintype "passive"))
    )
    (net (code "33") (name "Net-(R22-Pad1)") (class "Default")
      (node (ref "R22") (pin "1") (pinfunction "1_1") (pintype "passive"))
      (node (ref "SW1") (pin "2") (pinfunction "2_2") (pintype "passive"))
    )
    (net (code "34") (name "Net-(U3-OSC_IN)") (class "Default")
      (node (ref "U3") (pin "1") (pinfunction "OSC_IN_1") (pintype "passive"))
      (node (ref "X1") (pin "2") (pinfunction "2_2") (pintype "passive"))
    )
    (net (code "35") (name "Net-(U3-OSC_OUT)") (class "Default")
      (node (ref "U3") (pin "2") (pinfunction "OSC_OUT_2") (pintype "passive"))
      (node (ref "X1") (pin "1") (pinfunction "1_1") (pintype "passive"))
    )
    (net (code "36") (name "Net-(U3-VBAT)") (class "Default")
      (node (ref "C16") (pin "1") (pinfunction "1_1") (pintype "passive"))
      (node (ref "D5") (pin "1") (pinfunction "1_1") (pintype "power_in"))
      (node (ref "U3") (pin "3") (pinfunction "VBAT_3") (pintype "passive"))
    )
    (net (code "37") (name "Net-(U5-BOOT0)") (class "Default")
      (node (ref "R10") (pin "2") (pinfunction "2_2") (pintype "passive"))
      (node (ref "U5") (pin "44") (pinfunction "BOOT0_44") (pintype "passive"))
    )
    (net (code "38") (name "Net-(U5-OSC_IN)") (class "Default")
      (node (ref "C15") (pin "1") (pinfunction "1_1") (pintype "passive"))
      (node (ref "U5") (pin "5") (pinfunction "OSC_IN_5") (pintype "passive"))
      (node (ref "X2") (pin "3") (pinfunction "3_3") (pintype "passive"))
    )
    (net (code "39") (name "Net-(U5-OSC_OUT)") (class "Default")
      (node (ref "C19") (pin "1") (pinfunction "1_1") (pintype "passive"))
      (node (ref "U5") (pin "6") (pinfunction "OSC_OUT_6") (pintype "passive"))
      (node (ref "X2") (pin "1") (pinfunction "1_1") (pintype "passive"))
    )
    (net (code "40") (name "Net-(U5-PB0)") (class "Default")
      (node (ref "R8") (pin "1") (pinfunction "1_1") (pintype "passive"))
      (node (ref "U5") (pin "18") (pinfunction "PB0_18") (pintype "passive"))
    )
    (net (code "41") (name "Net-(U5-PB14)") (class "Default")
      (node (ref "R11") (pin "1") (pinfunction "1_1") (pintype "passive"))
      (node (ref "U5") (pin "27") (pinfunction "PB14_27") (pintype "passive"))
    )
    (net (code "42") (name "Net-(U6-SCLK)") (class "Default")
      (node (ref "R12") (pin "1") (pinfunction "1_1") (pintype "passive"))
      (node (ref "U6") (pin "1") (pinfunction "SCLK_1") (pintype "passive"))
    )
    (net (code "43") (name "Net-(U6-SIO)") (class "Default")
      (node (ref "R13") (pin "1") (pinfunction "1_1") (pintype "passive"))
      (node (ref "U6") (pin "3") (pinfunction "SIO_3") (pintype "passive"))
    )
    (net (code "44") (name "Net-(U6-~{CS})") (class "Default")
      (node (ref "R14") (pin "1") (pinfunction "1_1") (pintype "passive"))
      (node (ref "U6") (pin "2") (pinfunction "~{CS}_2") (pintype "passive"))
    )
    (net (code "45") (name "Net-(U6-~{OT})") (class "Default")
      (node (ref "R15") (pin "1") (pinfunction "1_1") (pintype "passive"))
      (node (ref "U6") (pin "5") (pinfunction "~{OT}_5") (pintype "passive"))
    )
    (net (code "46") (name "unconnected-(SW1-Pad3)") (class "Default")
      (node (ref "SW1") (pin "3") (pinfunction "3_3") (pintype "passive"))
    )
    (net (code "47") (name "unconnected-(U3-FT{slash}OUT-Pad7)") (class "Default")
      (node (ref "U3") (pin "7") (pinfunction "FT/OUT_7") (pintype "passive"))
    )
    (net (code "48") (name "unconnected-(U5-OSC32_IN-Pad3)") (class "Default")
      (node (ref "U5") (pin "3") (pinfunction "OSC32_IN_3") (pintype "passive"))
    )
    (net (code "49") (name "unconnected-(U5-OSC32_OUT-Pad4)") (class "Default")
      (node (ref "U5") (pin "4") (pinfunction "OSC32_OUT_4") (pintype "passive"))
    )
    (net (code "50") (name "unconnected-(U5-PA0_{slash}_WKP-Pad10)") (class "Default")
      (node (ref "U5") (pin "10") (pinfunction "PA0_/_WKP_10") (pintype "passive"))
    )
    (net (code "51") (name "unconnected-(U5-PA1-Pad11)") (class "Default")
      (node (ref "U5") (pin "11") (pinfunction "PA1_11") (pintype "passive"))
    )
    (net (code "52") (name "unconnected-(U5-PB3-Pad39)") (class "Default")
      (node (ref "U5") (pin "39") (pinfunction "PB3_39") (pintype "passive"))
    )
    (net (code "53") (name "unconnected-(U5-PB8-Pad45)") (class "Default")
      (node (ref "U5") (pin "45") (pinfunction "PB8_45") (pintype "passive"))
    )
    (net (code "54") (name "unconnected-(U5-PB12-Pad25)") (class "Default")
      (node (ref "U5") (pin "25") (pinfunction "PB12_25") (pintype "passive"))
    )
    (net (code "55") (name "unconnected-(U5-PB13-Pad26)") (class "Default")
      (node (ref "U5") (pin "26") (pinfunction "PB13_26") (pintype "passive"))
    )
    (net (code "56") (name "unconnected-(U5-PB15-Pad28)") (class "Default")
      (node (ref "U5") (pin "28") (pinfunction "PB15_28") (pintype "passive"))
    )
    (net (code "57") (name "unconnected-(U5-PC13-Pad2)") (class "Default")
      (node (ref "U5") (pin "2") (pinfunction "PC13_2") (pintype "passive"))
    )
    (net (code "58") (name "unconnected-(U5-SPI_MISO-Pad16)") (class "Default")
      (node (ref "U5") (pin "16") (pinfunction "SPI_MISO_16") (pintype "passive"))
    )
    (net (code "59") (name "unconnected-(U5-UART_CK-Pad29)") (class "Default")
      (node (ref "U5") (pin "29") (pinfunction "UART_CK_29") (pintype "passive"))
    )
    (net (code "60") (name "unconnected-(U5-UART_RX-Pad31)") (class "Default")
      (node (ref "U5") (pin "31") (pinfunction "UART_RX_31") (pintype "passive"))
    )
    (net (code "61") (name "unconnected-(U5-UART_TX-Pad30)") (class "Default")
      (node (ref "U5") (pin "30") (pinfunction "UART_TX_30") (pintype "passive"))
    )
    (net (code "62") (name "unconnected-(U5-VBAT-Pad1)") (class "Default")
      (node (ref "U5") (pin "1") (pinfunction "VBAT_1") (pintype "passive"))
    )
    (net (code "63") (name "unconnected-(U6-NC-Pad7)") (class "Default")
      (node (ref "U6") (pin "7") (pinfunction "NC_7") (pintype "passive"))
    )
    (net (code "64") (name "unconnected-(U6-~{ALERT}-Pad6)") (class "Default")
      (node (ref "U6") (pin "6") (pinfunction "~{ALERT}_6") (pintype "passive"))
    )
    (net (code "65") (name "unconnected-(U7-CLK-Pad20)") (class "Default")
      (node (ref "U7") (pin "20") (pinfunction "CLK_20") (pintype "passive"))
    )
    (net (code "66") (name "unconnected-(U7-CMD-Pad19)") (class "Default")
      (node (ref "U7") (pin "19") (pinfunction "CMD_19") (pintype "passive"))
    )
    (net (code "67") (name "unconnected-(U7-IO0-Pad25)") (class "Default")
      (node (ref "U7") (pin "25") (pinfunction "IO0_25") (pintype "passive"))
    )
    (net (code "68") (name "unconnected-(U7-IO2-Pad24)") (class "Default")
      (node (ref "U7") (pin "24") (pinfunction "IO2_24") (pintype "passive"))
    )
    (net (code "69") (name "unconnected-(U7-IO4-Pad26)") (class "Default")
      (node (ref "U7") (pin "26") (pinfunction "IO4_26") (pintype "passive"))
    )
    (net (code "70") (name "unconnected-(U7-IO5-Pad29)") (class "Default")
      (node (ref "U7") (pin "29") (pinfunction "IO5_29") (pintype "passive"))
    )
    (net (code "71") (name "unconnected-(U7-IO12-Pad14)") (class "Default")
      (node (ref "U7") (pin "14") (pinfunction "IO12_14") (pintype "passive"))
    )
    (net (code "72") (name "unconnected-(U7-IO13-Pad16)") (class "Default")
      (node (ref "U7") (pin "16") (pinfunction "IO13_16") (pintype "passive"))
    )
    (net (code "73") (name "unconnected-(U7-IO14-Pad13)") (class "Default")
      (node (ref "U7") (pin "13") (pinfunction "IO14_13") (pintype "passive"))
    )
    (net (code "74") (name "unconnected-(U7-IO15-Pad23)") (class "Default")
      (node (ref "U7") (pin "23") (pinfunction "IO15_23") (pintype "passive"))
    )
    (net (code "75") (name "unconnected-(U7-IO16-Pad27)") (class "Default")
      (node (ref "U7") (pin "27") (pinfunction "IO16_27") (pintype "passive"))
    )
    (net (code "76") (name "unconnected-(U7-IO17-Pad28)") (class "Default")
      (node (ref "U7") (pin "28") (pinfunction "IO17_28") (pintype "passive"))
    )
    (net (code "77") (name "unconnected-(U7-IO18-Pad30)") (class "Default")
      (node (ref "U7") (pin "30") (pinfunction "IO18_30") (pintype "passive"))
    )
    (net (code "78") (name "unconnected-(U7-IO19-Pad31)") (class "Default")
      (node (ref "U7") (pin "31") (pinfunction "IO19_31") (pintype "passive"))
    )
    (net (code "79") (name "unconnected-(U7-IO21-Pad33)") (class "Default")
      (node (ref "U7") (pin "33") (pinfunction "IO21_33") (pintype "passive"))
    )
    (net (code "80") (name "unconnected-(U7-IO22-Pad36)") (class "Default")
      (node (ref "U7") (pin "36") (pinfunction "IO22_36") (pintype "passive"))
    )
    (net (code "81") (name "unconnected-(U7-IO23-Pad37)") (class "Default")
      (node (ref "U7") (pin "37") (pinfunction "IO23_37") (pintype "passive"))
    )
    (net (code "82") (name "unconnected-(U7-IO25-Pad10)") (class "Default")
      (node (ref "U7") (pin "10") (pinfunction "IO25_10") (pintype "passive"))
    )
    (net (code "83") (name "unconnected-(U7-IO26-Pad11)") (class "Default")
      (node (ref "U7") (pin "11") (pinfunction "IO26_11") (pintype "passive"))
    )
    (net (code "84") (name "unconnected-(U7-IO27-Pad12)") (class "Default")
      (node (ref "U7") (pin "12") (pinfunction "IO27_12") (pintype "passive"))
    )
    (net (code "85") (name "unconnected-(U7-IO32-Pad8)") (class "Default")
      (node (ref "U7") (pin "8") (pinfunction "IO32_8") (pintype "passive"))
    )
    (net (code "86") (name "unconnected-(U7-IO33-Pad9)") (class "Default")
      (node (ref "U7") (pin "9") (pinfunction "IO33_9") (pintype "passive"))
    )
    (net (code "87") (name "unconnected-(U7-IO34-Pad6)") (class "Default")
      (node (ref "U7") (pin "6") (pinfunction "IO34_6") (pintype "passive"))
    )
    (net (code "88") (name "unconnected-(U7-IO35-Pad7)") (class "Default")
      (node (ref "U7") (pin "7") (pinfunction "IO35_7") (pintype "passive"))
    )
    (net (code "89") (name "unconnected-(U7-NC-Pad32)") (class "Default")
      (node (ref "U7") (pin "32") (pinfunction "NC_32") (pintype "passive"))
    )
    (net (code "90") (name "unconnected-(U7-SD0-Pad21)") (class "Default")
      (node (ref "U7") (pin "21") (pinfunction "SD0_21") (pintype "passive"))
    )
    (net (code "91") (name "unconnected-(U7-SD1-Pad22)") (class "Default")
      (node (ref "U7") (pin "22") (pinfunction "SD1_22") (pintype "passive"))
    )
    (net (code "92") (name "unconnected-(U7-SD2-Pad17)") (class "Default")
      (node (ref "U7") (pin "17") (pinfunction "SD2_17") (pintype "passive"))
    )
    (net (code "93") (name "unconnected-(U7-SD3-Pad18)") (class "Default")
      (node (ref "U7") (pin "18") (pinfunction "SD3_18") (pintype "passive"))
    )
    (net (code "94") (name "unconnected-(U7-SENSOR_VN-Pad5)") (class "Default")
      (node (ref "U7") (pin "5") (pinfunction "SENSOR_VN_5") (pintype "passive"))
    )
    (net (code "95") (name "unconnected-(U7-SENSOR_VP-Pad4)") (class "Default")
      (node (ref "U7") (pin "4") (pinfunction "SENSOR_VP_4") (pintype "passive"))
    )
  )
)
